# splitter.net
KiCad netlist of a schematic drawn in EAGLE
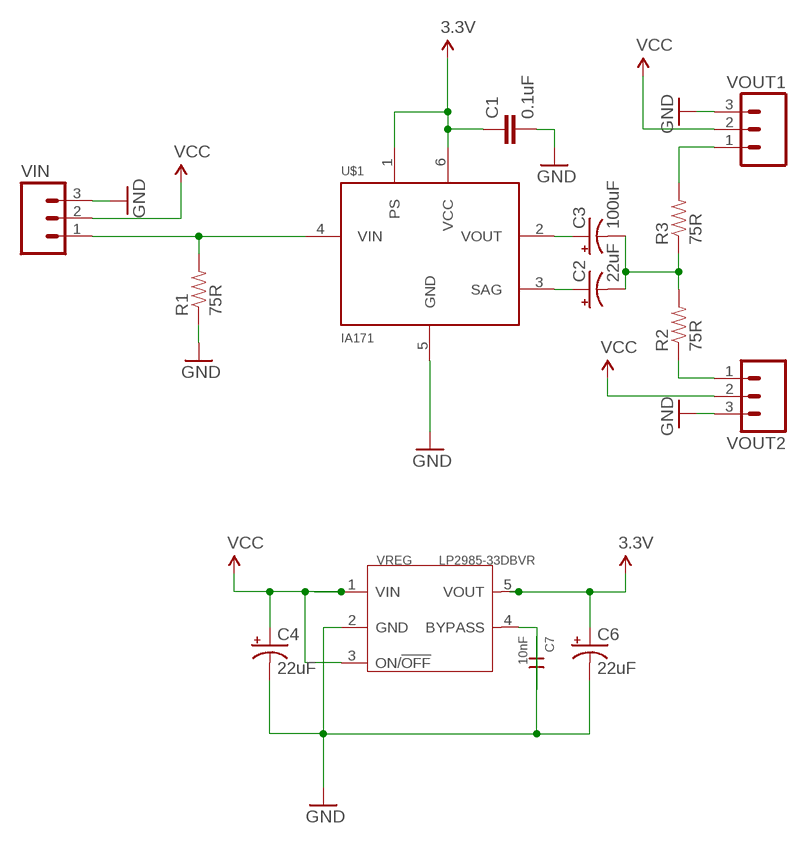
[diagram p0: schematic, sheet 1]

(export (version "E")
  (design (tool "Eeschema 10.0.6"))
  (components
    (comp (ref "C1")
      (value "0.1uF")
      (footprint "eagle-import:0805")
      (libsource (lib "eagle-import") (part "CAP0805"))
    )
    (comp (ref "C2")
      (value "22uF")
      (footprint "eagle-import:EIA3216")
      (libsource (lib "eagle-import") (part "CAP_POL1206"))
    )
    (comp (ref "C3")
      (value "100uF")
      (footprint "eagle-import:EIA3528")
      (libsource (lib "eagle-import") (part "CAP_POL3528"))
    )
    (comp (ref "C4")
      (value "22uF")
      (footprint "eagle-import:EIA3216")
      (libsource (lib "eagle-import") (part "CAP_POL1206"))
    )
    (comp (ref "C6")
      (value "22uF")
      (footprint "eagle-import:EIA3216")
      (libsource (lib "eagle-import") (part "CAP_POL1206"))
    )
    (comp (ref "C7")
      (value "10nF")
      (footprint "eagle-import:C0805")
      (fields (field (name "MPN") "CC0805JRX7R9BB103"))
      (libsource (lib "eagle-import") (part "CERAMIC-10NF-50V-5%-X7R(0805)"))
    )
    (comp (ref "R1")
      (value "75R")
      (footprint "eagle-import:0805")
      (libsource (lib "eagle-import") (part "RESISTOR0805-RES"))
    )
    (comp (ref "R2")
      (value "75R")
      (footprint "eagle-import:0805")
      (libsource (lib "eagle-import") (part "RESISTOR0805-RES"))
    )
    (comp (ref "R3")
      (value "75R")
      (footprint "eagle-import:0805")
      (libsource (lib "eagle-import") (part "RESISTOR0805-RES"))
    )
    (comp (ref "U$1")
      (value "IA171")
      (footprint "eagle-import:SOT23-6")
      (libsource (lib "eagle-import") (part "IA171"))
    )
    (comp (ref "VIN")
      (value "M03LOCK")
      (footprint "eagle-import:1X03_LOCK")
      (libsource (lib "eagle-import") (part "M03LOCK"))
    )
    (comp (ref "VOUT1")
      (value "M03LOCK")
      (footprint "eagle-import:1X03_LOCK")
      (libsource (lib "eagle-import") (part "M03LOCK"))
    )
    (comp (ref "VOUT2")
      (value "M03LOCK")
      (footprint "eagle-import:1X03_LOCK")
      (libsource (lib "eagle-import") (part "M03LOCK"))
    )
    (comp (ref "VREG")
      (value "LP2985-33DBVR")
      (footprint "eagle-import:SOT-23-5")
      (libsource (lib "eagle-import") (part "PMIC-LP2985-33DBVR(SOT23-5)"))
    )
  )
  (nets
    (net (code "1") (name "3.3V") (class "Default")
      (node (ref "C1") (pin "1") (pinfunction "1_1") (pintype "passive"))
      (node (ref "C6") (pin "A") (pinfunction "+_A") (pintype "passive"))
      (node (ref "U$1") (pin "1") (pinfunction "PS_1") (pintype "bidirectional"))
      (node (ref "U$1") (pin "6") (pinfunction "VCC_6") (pintype "bidirectional"))
      (node (ref "VREG") (pin "5") (pinfunction "VOUT_5") (pintype "bidirectional"))
    )
    (net (code "2") (name "GND") (class "Default")
      (node (ref "C1") (pin "2") (pinfunction "2_2") (pintype "passive"))
      (node (ref "C4") (pin "C") (pinfunction "-_C") (pintype "passive"))
      (node (ref "C6") (pin "C") (pinfunction "-_C") (pintype "passive"))
      (node (ref "C7") (pin "1") (pinfunction "1_1") (pintype "passive"))
      (node (ref "R1") (pin "1") (pinfunction "1_1") (pintype "passive"))
      (node (ref "U$1") (pin "5") (pinfunction "GND_5") (pintype "bidirectional"))
      (node (ref "VIN") (pin "3") (pinfunction "3_3") (pintype "passive"))
      (node (ref "VOUT1") (pin "3") (pinfunction "3_3") (pintype "passive"))
      (node (ref "VOUT2") (pin "3") (pinfunction "3_3") (pintype "passive"))
      (node (ref "VREG") (pin "2") (pinfunction "GND_2") (pintype "bidirectional"))
    )
    (net (code "3") (name "Net-(C2-+)") (class "Default")
      (node (ref "C2") (pin "A") (pinfunction "+_A") (pintype "passive"))
      (node (ref "U$1") (pin "3") (pinfunction "SAG_3") (pintype "bidirectional"))
    )
    (net (code "4") (name "Net-(C2--)") (class "Default")
      (node (ref "C2") (pin "C") (pinfunction "-_C") (pintype "passive"))
      (node (ref "C3") (pin "C") (pinfunction "-_C") (pintype "passive"))
      (node (ref "R2") (pin "2") (pinfunction "2_2") (pintype "passive"))
      (node (ref "R3") (pin "1") (pinfunction "1_1") (pintype "passive"))
    )
    (net (code "5") (name "Net-(C3-+)") (class "Default")
      (node (ref "C3") (pin "A") (pinfunction "+_A") (pintype "passive"))
      (node (ref "U$1") (pin "2") (pinfunction "VOUT_2") (pintype "bidirectional"))
    )
    (net (code "6") (name "Net-(R2-Pad1)") (class "Default")
      (node (ref "R2") (pin "1") (pinfunction "1_1") (pintype "passive"))
      (node (ref "VOUT2") (pin "1") (pinfunction "1_1") (pintype "passive"))
    )
    (net (code "7") (name "Net-(R3-Pad2)") (class "Default")
      (node (ref "R3") (pin "2") (pinfunction "2_2") (pintype "passive"))
      (node (ref "VOUT1") (pin "1") (pinfunction "1_1") (pintype "passive"))
    )
    (net (code "8") (name "Net-(U$1-VIN)") (class "Default")
      (node (ref "R1") (pin "2") (pinfunction "2_2") (pintype "passive"))
      (node (ref "U$1") (pin "4") (pinfunction "VIN_4") (pintype "bidirectional"))
      (node (ref "VIN") (pin "1") (pinfunction "1_1") (pintype "passive"))
    )
    (net (code "9") (name "Net-(VREG-BYPASS)") (class "Default")
      (node (ref "C7") (pin "2") (pinfunction "2_2") (pintype "passive"))
      (node (ref "VREG") (pin "4") (pinfunction "BYPASS_4") (pintype "bidirectional"))
    )
    (net (code "10") (name "VCC") (class "Default")
      (node (ref "C4") (pin "A") (pinfunction "+_A") (pintype "passive"))
      (node (ref "VIN") (pin "2") (pinfunction "2_2") (pintype "passive"))
      (node (ref "VOUT1") (pin "2") (pinfunction "2_2") (pintype "passive"))
      (node (ref "VOUT2") (pin "2") (pinfunction "2_2") (pintype "passive"))
      (node (ref "VREG") (pin "1") (pinfunction "VIN_1") (pintype "bidirectional"))
      (node (ref "VREG") (pin "3") (pinfunction "ON/~{OFF}_3") (pintype "bidirectional"))
    )
  )
)
